# MeterMaid.net
KiCad netlist of a schematic drawn in EAGLE
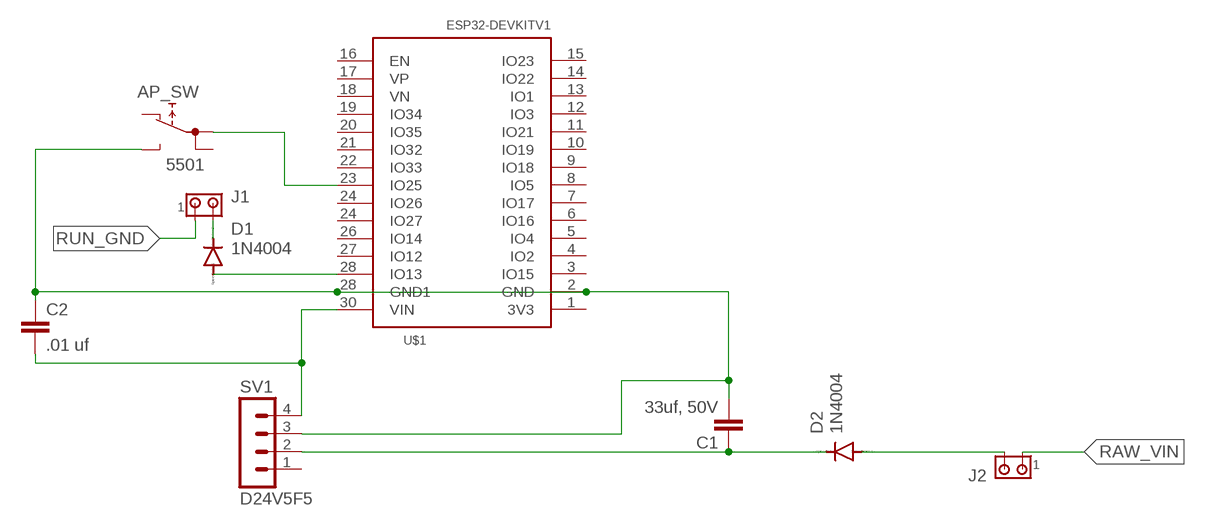
[diagram p0: schematic, sheet 1]

(export (version "E")
  (design (tool "Eeschema 10.0.6"))
  (components
    (comp (ref "AP_SW")
      (value "5501")
      (footprint "eagle-import:5501")
      (libsource (lib "eagle-import") (part "55?01"))
    )
    (comp (ref "C1")
      (value "33uf, 50V")
      (footprint "eagle-import:C050-030X075")
      (libsource (lib "eagle-import") (part "C-EU050-030X075"))
    )
    (comp (ref "C2")
      (value ".01 uf")
      (footprint "eagle-import:C2.5-3")
      (libsource (lib "eagle-import") (part "C2,5-3"))
    )
    (comp (ref "D1")
      (value "1N4004")
      (footprint "eagle-import:DO41-10")
      (libsource (lib "eagle-import") (part "1N4004"))
    )
    (comp (ref "D2")
      (value "1N4004")
      (footprint "eagle-import:DO41-10")
      (libsource (lib "eagle-import") (part "1N4004"))
    )
    (comp (ref "J1")
      (value "MTA02-156")
      (footprint "eagle-import:1X2MTA")
      (libsource (lib "eagle-import") (part "MTA02-156"))
    )
    (comp (ref "J2")
      (value "MTA02-156")
      (footprint "eagle-import:1X2MTA")
      (libsource (lib "eagle-import") (part "MTA02-156"))
    )
    (comp (ref "SV1")
      (value "D24V5F5")
      (footprint "eagle-import:MA04-1")
      (libsource (lib "eagle-import") (part "MA04-1"))
    )
    (comp (ref "U$1")
      (value "ESP32DEVKITV1")
      (footprint "eagle-import:ESP32-DEVKITV1")
      (libsource (lib "eagle-import") (part "ESP32DEVKITV1"))
    )
  )
  (nets
    (net (code "1") (name "Net-(C1-Pad1)") (class "Default")
      (node (ref "C1") (pin "1") (pinfunction "1_1") (pintype "passive"))
      (node (ref "D2") (pin "C") (pinfunction "C_C") (pintype "passive"))
      (node (ref "SV1") (pin "2") (pinfunction "2_2") (pintype "passive"))
    )
    (net (code "2") (name "Net-(D1-PadC)") (class "Default")
      (node (ref "D1") (pin "C") (pinfunction "C_C") (pintype "passive"))
      (node (ref "J1") (pin "2") (pinfunction "2_2") (pintype "passive"))
    )
    (net (code "3") (name "Net-(D2-PadA)") (class "Default")
      (node (ref "D2") (pin "A") (pinfunction "A_A") (pintype "passive"))
      (node (ref "J2") (pin "2") (pinfunction "2_2") (pintype "passive"))
    )
    (net (code "4") (name "Net-(U$1-GND)") (class "Default")
      (node (ref "AP_SW") (pin "NO") (pinfunction "NO_NO") (pintype "passive"))
      (node (ref "C1") (pin "2") (pinfunction "2_2") (pintype "passive"))
      (node (ref "C2") (pin "1") (pinfunction "1_1") (pintype "passive"))
      (node (ref "SV1") (pin "3") (pinfunction "3_3") (pintype "passive"))
      (node (ref "U$1") (pin "2") (pinfunction "GND_2") (pintype "bidirectional"))
      (node (ref "U$1") (pin "28") (pinfunction "GND1_28") (pintype "bidirectional"))
    )
    (net (code "5") (name "Net-(U$1-IO13)") (class "Default")
      (node (ref "D1") (pin "A") (pinfunction "A_A") (pintype "passive"))
      (node (ref "U$1") (pin "28") (pinfunction "IO13_28") (pintype "bidirectional"))
    )
    (net (code "6") (name "Net-(U$1-IO25)") (class "Default")
      (node (ref "AP_SW") (pin "1A") (pinfunction "1A_1A") (pintype "passive"))
      (node (ref "U$1") (pin "23") (pinfunction "IO25_23") (pintype "bidirectional"))
    )
    (net (code "7") (name "Net-(U$1-VIN)") (class "Default")
      (node (ref "C2") (pin "2") (pinfunction "2_2") (pintype "passive"))
      (node (ref "SV1") (pin "4") (pinfunction "4_4") (pintype "passive"))
      (node (ref "U$1") (pin "30") (pinfunction "VIN_30") (pintype "bidirectional"))
    )
    (net (code "8") (name "RAW_VIN") (class "Default")
      (node (ref "J2") (pin "1") (pinfunction "1_1") (pintype "passive"))
    )
    (net (code "9") (name "RUN_GND") (class "Default")
      (node (ref "J1") (pin "1") (pinfunction "1_1") (pintype "passive"))
    )
    (net (code "10") (name "unconnected-(AP_SW-Pad1B)") (class "Default")
      (node (ref "AP_SW") (pin "1B") (pinfunction "1B_1B") (pintype "passive"))
    )
    (net (code "11") (name "unconnected-(AP_SW-PadNC)") (class "Default")
      (node (ref "AP_SW") (pin "NC") (pinfunction "NC_NC") (pintype "passive"))
    )
    (net (code "12") (name "unconnected-(SV1-Pad1)") (class "Default")
      (node (ref "SV1") (pin "1") (pinfunction "1_1") (pintype "passive"))
    )
    (net (code "13") (name "unconnected-(U$1-3V3-Pad1)") (class "Default")
      (node (ref "U$1") (pin "1") (pinfunction "3V3_1") (pintype "bidirectional"))
    )
    (net (code "14") (name "unconnected-(U$1-EN-Pad16)") (class "Default")
      (node (ref "U$1") (pin "16") (pinfunction "EN_16") (pintype "bidirectional"))
    )
    (net (code "15") (name "unconnected-(U$1-IO1-Pad13)") (class "Default")
      (node (ref "U$1") (pin "13") (pinfunction "IO1_13") (pintype "bidirectional"))
    )
    (net (code "16") (name "unconnected-(U$1-IO2-Pad4)") (class "Default")
      (node (ref "U$1") (pin "4") (pinfunction "IO2_4") (pintype "bidirectional"))
    )
    (net (code "17") (name "unconnected-(U$1-IO3-Pad12)") (class "Default")
      (node (ref "U$1") (pin "12") (pinfunction "IO3_12") (pintype "bidirectional"))
    )
    (net (code "18") (name "unconnected-(U$1-IO4-Pad5)") (class "Default")
      (node (ref "U$1") (pin "5") (pinfunction "IO4_5") (pintype "bidirectional"))
    )
    (net (code "19") (name "unconnected-(U$1-IO5-Pad8)") (class "Default")
      (node (ref "U$1") (pin "8") (pinfunction "IO5_8") (pintype "bidirectional"))
    )
    (net (code "20") (name "unconnected-(U$1-IO12-Pad27)") (class "Default")
      (node (ref "U$1") (pin "27") (pinfunction "IO12_27") (pintype "bidirectional"))
    )
    (net (code "21") (name "unconnected-(U$1-IO14-Pad26)") (class "Default")
      (node (ref "U$1") (pin "26") (pinfunction "IO14_26") (pintype "bidirectional"))
    )
    (net (code "22") (name "unconnected-(U$1-IO15-Pad3)") (class "Default")
      (node (ref "U$1") (pin "3") (pinfunction "IO15_3") (pintype "bidirectional"))
    )
    (net (code "23") (name "unconnected-(U$1-IO16-Pad6)") (class "Default")
      (node (ref "U$1") (pin "6") (pinfunction "IO16_6") (pintype "bidirectional"))
    )
    (net (code "24") (name "unconnected-(U$1-IO17-Pad7)") (class "Default")
      (node (ref "U$1") (pin "7") (pinfunction "IO17_7") (pintype "bidirectional"))
    )
    (net (code "25") (name "unconnected-(U$1-IO18-Pad9)") (class "Default")
      (node (ref "U$1") (pin "9") (pinfunction "IO18_9") (pintype "bidirectional"))
    )
    (net (code "26") (name "unconnected-(U$1-IO19-Pad10)") (class "Default")
      (node (ref "U$1") (pin "10") (pinfunction "IO19_10") (pintype "bidirectional"))
    )
    (net (code "27") (name "unconnected-(U$1-IO21-Pad11)") (class "Default")
      (node (ref "U$1") (pin "11") (pinfunction "IO21_11") (pintype "bidirectional"))
    )
    (net (code "28") (name "unconnected-(U$1-IO22-Pad14)") (class "Default")
      (node (ref "U$1") (pin "14") (pinfunction "IO22_14") (pintype "bidirectional"))
    )
    (net (code "29") (name "unconnected-(U$1-IO23-Pad15)") (class "Default")
      (node (ref "U$1") (pin "15") (pinfunction "IO23_15") (pintype "bidirectional"))
    )
    (net (code "30") (name "unconnected-(U$1-IO26-Pad24)") (class "Default")
      (node (ref "U$1") (pin "24") (pinfunction "IO26_24") (pintype "bidirectional"))
    )
    (net (code "31") (name "unconnected-(U$1-IO27-Pad24)") (class "Default")
      (node (ref "U$1") (pin "24") (pinfunction "IO27_24") (pintype "bidirectional"))
    )
    (net (code "32") (name "unconnected-(U$1-IO32-Pad21)") (class "Default")
      (node (ref "U$1") (pin "21") (pinfunction "IO32_21") (pintype "bidirectional"))
    )
    (net (code "33") (name "unconnected-(U$1-IO33-Pad22)") (class "Default")
      (node (ref "U$1") (pin "22") (pinfunction "IO33_22") (pintype "bidirectional"))
    )
    (net (code "34") (name "unconnected-(U$1-IO34-Pad19)") (class "Default")
      (node (ref "U$1") (pin "19") (pinfunction "IO34_19") (pintype "bidirectional"))
    )
    (net (code "35") (name "unconnected-(U$1-IO35-Pad20)") (class "Default")
      (node (ref "U$1") (pin "20") (pinfunction "IO35_20") (pintype "bidirectional"))
    )
    (net (code "36") (name "unconnected-(U$1-VN-Pad18)") (class "Default")
      (node (ref "U$1") (pin "18") (pinfunction "VN_18") (pintype "bidirectional"))
    )
    (net (code "37") (name "unconnected-(U$1-VP-Pad17)") (class "Default")
      (node (ref "U$1") (pin "17") (pinfunction "VP_17") (pintype "bidirectional"))
    )
  )
)
